# Power_Board_2.net
KiCad netlist of a schematic drawn in Altium Designer
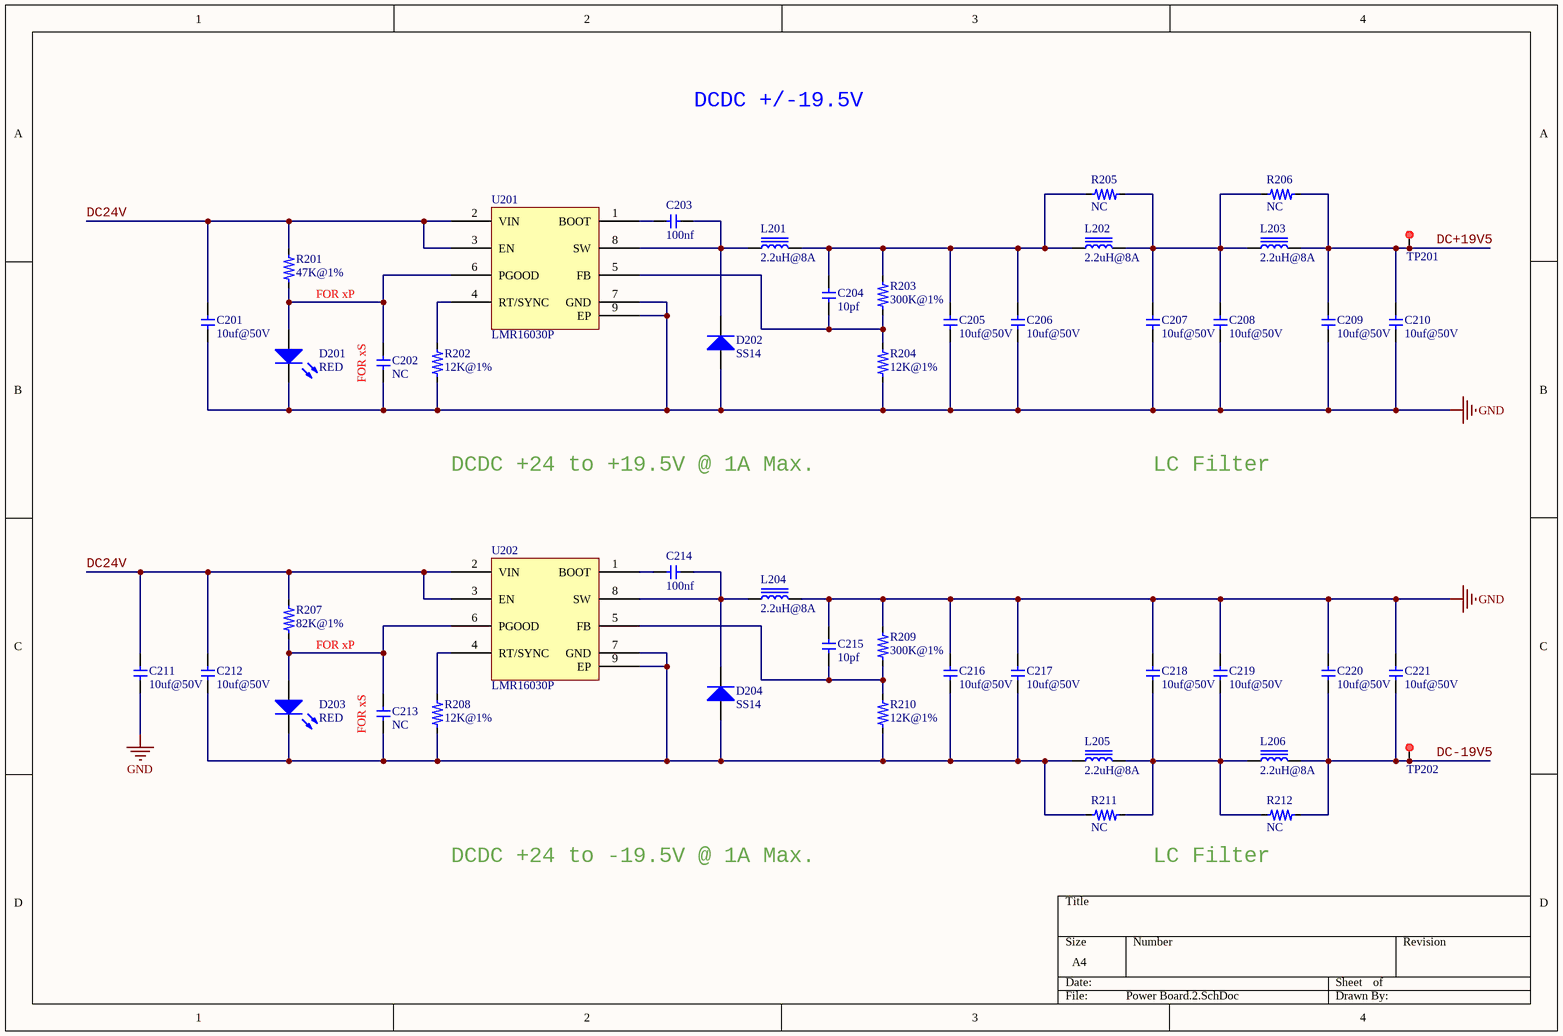
[diagram p0: Power Board.2.SchDoc]

(export (version "E")
  (design (tool "Eeschema 10.0.6"))
  (components
    (comp (ref "C201")
      (value "10uf@50V")
      (footprint "C1206")
      (fields (field (name "Comment") "Cap"))
      (libsource (lib "carrot_lib") (part "Cap"))
    )
    (comp (ref "C202")
      (value "NC")
      (footprint "C0603")
      (fields (field (name "Comment") "Cap"))
      (libsource (lib "carrot_lib") (part "Cap"))
    )
    (comp (ref "C203")
      (value "100nf")
      (footprint "C0603")
      (fields (field (name "Comment") "Cap"))
      (libsource (lib "carrot_lib") (part "Cap"))
    )
    (comp (ref "C204")
      (value "10pf")
      (footprint "C0603")
      (fields (field (name "Comment") "Cap"))
      (libsource (lib "carrot_lib") (part "Cap"))
    )
    (comp (ref "C205")
      (value "10uf@50V")
      (footprint "C1206")
      (fields (field (name "Comment") "Cap"))
      (libsource (lib "carrot_lib") (part "Cap"))
    )
    (comp (ref "C206")
      (value "10uf@50V")
      (footprint "C1206")
      (fields (field (name "Comment") "Cap"))
      (libsource (lib "carrot_lib") (part "Cap"))
    )
    (comp (ref "C207")
      (value "10uf@50V")
      (footprint "C1206")
      (fields (field (name "Comment") "Cap"))
      (libsource (lib "carrot_lib") (part "Cap"))
    )
    (comp (ref "C208")
      (value "10uf@50V")
      (footprint "C1206")
      (fields (field (name "Comment") "Cap"))
      (libsource (lib "carrot_lib") (part "Cap"))
    )
    (comp (ref "C209")
      (value "10uf@50V")
      (footprint "C1206")
      (fields (field (name "Comment") "Cap"))
      (libsource (lib "carrot_lib") (part "Cap"))
    )
    (comp (ref "C210")
      (value "10uf@50V")
      (footprint "C1206")
      (fields (field (name "Comment") "Cap"))
      (libsource (lib "carrot_lib") (part "Cap"))
    )
    (comp (ref "C211")
      (value "10uf@50V")
      (footprint "C1206")
      (fields (field (name "Comment") "Cap"))
      (libsource (lib "carrot_lib") (part "Cap"))
    )
    (comp (ref "C212")
      (value "10uf@50V")
      (footprint "C1206")
      (fields (field (name "Comment") "Cap"))
      (libsource (lib "carrot_lib") (part "Cap"))
    )
    (comp (ref "C213")
      (value "NC")
      (footprint "C0603")
      (fields (field (name "Comment") "Cap"))
      (libsource (lib "carrot_lib") (part "Cap"))
    )
    (comp (ref "C214")
      (value "100nf")
      (footprint "C0603")
      (fields (field (name "Comment") "Cap"))
      (libsource (lib "carrot_lib") (part "Cap"))
    )
    (comp (ref "C215")
      (value "10pf")
      (footprint "C0603")
      (fields (field (name "Comment") "Cap"))
      (libsource (lib "carrot_lib") (part "Cap"))
    )
    (comp (ref "C216")
      (value "10uf@50V")
      (footprint "C1206")
      (fields (field (name "Comment") "Cap"))
      (libsource (lib "carrot_lib") (part "Cap"))
    )
    (comp (ref "C217")
      (value "10uf@50V")
      (footprint "C1206")
      (fields (field (name "Comment") "Cap"))
      (libsource (lib "carrot_lib") (part "Cap"))
    )
    (comp (ref "C218")
      (value "10uf@50V")
      (footprint "C1206")
      (fields (field (name "Comment") "Cap"))
      (libsource (lib "carrot_lib") (part "Cap"))
    )
    (comp (ref "C219")
      (value "10uf@50V")
      (footprint "C1206")
      (fields (field (name "Comment") "Cap"))
      (libsource (lib "carrot_lib") (part "Cap"))
    )
    (comp (ref "C220")
      (value "10uf@50V")
      (footprint "C1206")
      (fields (field (name "Comment") "Cap"))
      (libsource (lib "carrot_lib") (part "Cap"))
    )
    (comp (ref "C221")
      (value "10uf@50V")
      (footprint "C1206")
      (fields (field (name "Comment") "Cap"))
      (libsource (lib "carrot_lib") (part "Cap"))
    )
    (comp (ref "D201")
      (value "RED")
      (footprint "LED0603")
      (fields (field (name "Comment") "LED"))
      (libsource (lib "carrot_lib") (part "LED"))
    )
    (comp (ref "D202")
      (value "SS14")
      (footprint "DIODE-SMAF")
      (description "通用二极管")
      (fields (field (name "Comment") "Diode"))
      (libsource (lib "carrot_lib") (part "Diode"))
    )
    (comp (ref "D203")
      (value "RED")
      (footprint "LED0603")
      (fields (field (name "Comment") "LED"))
      (libsource (lib "carrot_lib") (part "LED"))
    )
    (comp (ref "D204")
      (value "SS14")
      (footprint "DIODE-SMAF")
      (description "通用二极管")
      (fields (field (name "Comment") "Diode"))
      (libsource (lib "carrot_lib") (part "Diode"))
    )
    (comp (ref "L201")
      (value "2.2uH@8A")
      (footprint "L06063")
      (description "Magnetic-Core Inductor")
      (fields (field (name "Comment") "Inductor Iron"))
      (libsource (lib "carrot_lib") (part "Inductor Iron"))
    )
    (comp (ref "L202")
      (value "2.2uH@8A")
      (footprint "L06063")
      (description "Magnetic-Core Inductor")
      (fields (field (name "Comment") "Inductor Iron"))
      (libsource (lib "carrot_lib") (part "Inductor Iron"))
    )
    (comp (ref "L203")
      (value "2.2uH@8A")
      (footprint "L06063")
      (description "Magnetic-Core Inductor")
      (fields (field (name "Comment") "Inductor Iron"))
      (libsource (lib "carrot_lib") (part "Inductor Iron"))
    )
    (comp (ref "L204")
      (value "2.2uH@8A")
      (footprint "L06063")
      (description "Magnetic-Core Inductor")
      (fields (field (name "Comment") "Inductor Iron"))
      (libsource (lib "carrot_lib") (part "Inductor Iron"))
    )
    (comp (ref "L205")
      (value "2.2uH@8A")
      (footprint "L06063")
      (description "Magnetic-Core Inductor")
      (fields (field (name "Comment") "Inductor Iron"))
      (libsource (lib "carrot_lib") (part "Inductor Iron"))
    )
    (comp (ref "L206")
      (value "2.2uH@8A")
      (footprint "L06063")
      (description "Magnetic-Core Inductor")
      (fields (field (name "Comment") "Inductor Iron"))
      (libsource (lib "carrot_lib") (part "Inductor Iron"))
    )
    (comp (ref "R201")
      (value "47K@1%")
      (footprint "R0603")
      (description "电阻")
      (fields (field (name "Comment") "Res"))
      (libsource (lib "carrot_lib") (part "Res"))
    )
    (comp (ref "R202")
      (value "12K@1%")
      (footprint "R0603")
      (description "电阻")
      (fields (field (name "Comment") "Res"))
      (libsource (lib "carrot_lib") (part "Res"))
    )
    (comp (ref "R203")
      (value "300K@1%")
      (footprint "R0603")
      (description "电阻")
      (fields (field (name "Comment") "Res"))
      (libsource (lib "carrot_lib") (part "Res"))
    )
    (comp (ref "R204")
      (value "12K@1%")
      (footprint "R0603")
      (description "电阻")
      (fields (field (name "Comment") "Res"))
      (libsource (lib "carrot_lib") (part "Res"))
    )
    (comp (ref "R205")
      (value "NC")
      (footprint "R0603")
      (description "电阻")
      (fields (field (name "Comment") "Res"))
      (libsource (lib "carrot_lib") (part "Res"))
    )
    (comp (ref "R206")
      (value "NC")
      (footprint "R0603")
      (description "电阻")
      (fields (field (name "Comment") "Res"))
      (libsource (lib "carrot_lib") (part "Res"))
    )
    (comp (ref "R207")
      (value "82K@1%")
      (footprint "R0603")
      (description "电阻")
      (fields (field (name "Comment") "Res"))
      (libsource (lib "carrot_lib") (part "Res"))
    )
    (comp (ref "R208")
      (value "12K@1%")
      (footprint "R0603")
      (description "电阻")
      (fields (field (name "Comment") "Res"))
      (libsource (lib "carrot_lib") (part "Res"))
    )
    (comp (ref "R209")
      (value "300K@1%")
      (footprint "R0603")
      (description "电阻")
      (fields (field (name "Comment") "Res"))
      (libsource (lib "carrot_lib") (part "Res"))
    )
    (comp (ref "R210")
      (value "12K@1%")
      (footprint "R0603")
      (description "电阻")
      (fields (field (name "Comment") "Res"))
      (libsource (lib "carrot_lib") (part "Res"))
    )
    (comp (ref "R211")
      (value "NC")
      (footprint "R0603")
      (description "电阻")
      (fields (field (name "Comment") "Res"))
      (libsource (lib "carrot_lib") (part "Res"))
    )
    (comp (ref "R212")
      (value "NC")
      (footprint "R0603")
      (description "电阻")
      (fields (field (name "Comment") "Res"))
      (libsource (lib "carrot_lib") (part "Res"))
    )
    (comp (ref "TP201")
      (value "TestPoint")
      (footprint "TestPoint-SMD100")
      (description "测试点")
      (libsource (lib "carrot_lib") (part "TestPoint"))
    )
    (comp (ref "TP202")
      (value "TestPoint")
      (footprint "TestPoint-SMD100")
      (description "测试点")
      (libsource (lib "carrot_lib") (part "TestPoint"))
    )
    (comp (ref "U201")
      (value "LMR16030P")
      (footprint "LMR16030-SOIC8")
      (description "LMR16030 SIMPLE SWITCHER® 60-V, 3-A Step-Down Converter With 40-µA IQ")
      (libsource (lib "carrot_lib") (part "LMR16030P"))
    )
    (comp (ref "U202")
      (value "LMR16030P")
      (footprint "LMR16030-SOIC8")
      (description "LMR16030 SIMPLE SWITCHER® 60-V, 3-A Step-Down Converter With 40-µA IQ")
      (libsource (lib "carrot_lib") (part "LMR16030P"))
    )
  )
  (nets
    (net (code "1") (name "/DC+19V5") (class "Default")
      (node (ref "C209") (pin "2") (pinfunction "2_2") (pintype "passive"))
      (node (ref "C210") (pin "2") (pinfunction "2_2") (pintype "passive"))
      (node (ref "L203") (pin "2") (pinfunction "2_2") (pintype "passive"))
      (node (ref "R206") (pin "1") (pinfunction "1_1") (pintype "passive"))
      (node (ref "TP201") (pin "1") (pinfunction "1_1") (pintype "passive"))
    )
    (net (code "2") (name "/DC-19V5") (class "Default")
      (node (ref "C220") (pin "1") (pinfunction "1_1") (pintype "passive"))
      (node (ref "C221") (pin "1") (pinfunction "1_1") (pintype "passive"))
      (node (ref "L206") (pin "2") (pinfunction "2_2") (pintype "passive"))
      (node (ref "R212") (pin "1") (pinfunction "1_1") (pintype "passive"))
      (node (ref "TP202") (pin "1") (pinfunction "1_1") (pintype "passive"))
    )
    (net (code "3") (name "/DC24V") (class "Default")
      (node (ref "C201") (pin "2") (pinfunction "2_2") (pintype "passive"))
      (node (ref "C211") (pin "2") (pinfunction "2_2") (pintype "passive"))
      (node (ref "C212") (pin "2") (pinfunction "2_2") (pintype "passive"))
      (node (ref "R201") (pin "2") (pinfunction "2_2") (pintype "passive"))
      (node (ref "R207") (pin "2") (pinfunction "2_2") (pintype "passive"))
      (node (ref "U201") (pin "2") (pinfunction "VIN_2") (pintype "passive"))
      (node (ref "U201") (pin "3") (pinfunction "EN_3") (pintype "passive"))
      (node (ref "U202") (pin "2") (pinfunction "VIN_2") (pintype "passive"))
      (node (ref "U202") (pin "3") (pinfunction "EN_3") (pintype "passive"))
    )
    (net (code "4") (name "GND") (class "Default")
      (node (ref "C201") (pin "1") (pinfunction "1_1") (pintype "passive"))
      (node (ref "C202") (pin "1") (pinfunction "1_1") (pintype "passive"))
      (node (ref "C205") (pin "1") (pinfunction "1_1") (pintype "passive"))
      (node (ref "C206") (pin "1") (pinfunction "1_1") (pintype "passive"))
      (node (ref "C207") (pin "1") (pinfunction "1_1") (pintype "passive"))
      (node (ref "C208") (pin "1") (pinfunction "1_1") (pintype "passive"))
      (node (ref "C209") (pin "1") (pinfunction "1_1") (pintype "passive"))
      (node (ref "C210") (pin "1") (pinfunction "1_1") (pintype "passive"))
      (node (ref "C211") (pin "1") (pinfunction "1_1") (pintype "passive"))
      (node (ref "C215") (pin "1") (pinfunction "1_1") (pintype "passive"))
      (node (ref "C216") (pin "2") (pinfunction "2_2") (pintype "passive"))
      (node (ref "C217") (pin "2") (pinfunction "2_2") (pintype "passive"))
      (node (ref "C218") (pin "2") (pinfunction "2_2") (pintype "passive"))
      (node (ref "C219") (pin "2") (pinfunction "2_2") (pintype "passive"))
      (node (ref "C220") (pin "2") (pinfunction "2_2") (pintype "passive"))
      (node (ref "C221") (pin "2") (pinfunction "2_2") (pintype "passive"))
      (node (ref "D201") (pin "2") (pinfunction "K_2") (pintype "passive"))
      (node (ref "D202") (pin "1") (pinfunction "A_1") (pintype "passive"))
      (node (ref "L204") (pin "2") (pinfunction "2_2") (pintype "passive"))
      (node (ref "R202") (pin "1") (pinfunction "1_1") (pintype "passive"))
      (node (ref "R204") (pin "1") (pinfunction "1_1") (pintype "passive"))
      (node (ref "R209") (pin "2") (pinfunction "2_2") (pintype "passive"))
      (node (ref "U201") (pin "7") (pinfunction "GND_7") (pintype "passive"))
      (node (ref "U201") (pin "9") (pinfunction "EP_9") (pintype "passive"))
    )
    (net (code "5") (name "Net-(C204-Pad1)") (class "Default")
      (node (ref "C204") (pin "1") (pinfunction "1_1") (pintype "passive"))
      (node (ref "C205") (pin "2") (pinfunction "2_2") (pintype "passive"))
      (node (ref "C206") (pin "2") (pinfunction "2_2") (pintype "passive"))
      (node (ref "L201") (pin "2") (pinfunction "2_2") (pintype "passive"))
      (node (ref "L202") (pin "1") (pinfunction "1_1") (pintype "passive"))
      (node (ref "R203") (pin "2") (pinfunction "2_2") (pintype "passive"))
      (node (ref "R205") (pin "2") (pinfunction "2_2") (pintype "passive"))
    )
    (net (code "6") (name "Net-(C207-Pad2)") (class "Default")
      (node (ref "C207") (pin "2") (pinfunction "2_2") (pintype "passive"))
      (node (ref "C208") (pin "2") (pinfunction "2_2") (pintype "passive"))
      (node (ref "L202") (pin "2") (pinfunction "2_2") (pintype "passive"))
      (node (ref "L203") (pin "1") (pinfunction "1_1") (pintype "passive"))
      (node (ref "R205") (pin "1") (pinfunction "1_1") (pintype "passive"))
      (node (ref "R206") (pin "2") (pinfunction "2_2") (pintype "passive"))
    )
    (net (code "7") (name "Net-(C218-Pad1)") (class "Default")
      (node (ref "C218") (pin "1") (pinfunction "1_1") (pintype "passive"))
      (node (ref "C219") (pin "1") (pinfunction "1_1") (pintype "passive"))
      (node (ref "L205") (pin "2") (pinfunction "2_2") (pintype "passive"))
      (node (ref "L206") (pin "1") (pinfunction "1_1") (pintype "passive"))
      (node (ref "R211") (pin "1") (pinfunction "1_1") (pintype "passive"))
      (node (ref "R212") (pin "2") (pinfunction "2_2") (pintype "passive"))
    )
    (net (code "8") (name "Net-(D201-A)") (class "Default")
      (node (ref "C202") (pin "2") (pinfunction "2_2") (pintype "passive"))
      (node (ref "D201") (pin "1") (pinfunction "A_1") (pintype "passive"))
      (node (ref "R201") (pin "1") (pinfunction "1_1") (pintype "passive"))
      (node (ref "U201") (pin "6") (pinfunction "PGOOD_6") (pintype "passive"))
    )
    (net (code "9") (name "Net-(D202-K)") (class "Default")
      (node (ref "C203") (pin "1") (pinfunction "1_1") (pintype "passive"))
      (node (ref "D202") (pin "2") (pinfunction "K_2") (pintype "passive"))
      (node (ref "L201") (pin "1") (pinfunction "1_1") (pintype "passive"))
      (node (ref "U201") (pin "8") (pinfunction "SW_8") (pintype "passive"))
    )
    (net (code "10") (name "Net-(D203-A)") (class "Default")
      (node (ref "C213") (pin "2") (pinfunction "2_2") (pintype "passive"))
      (node (ref "D203") (pin "1") (pinfunction "A_1") (pintype "passive"))
      (node (ref "R207") (pin "1") (pinfunction "1_1") (pintype "passive"))
      (node (ref "U202") (pin "6") (pinfunction "PGOOD_6") (pintype "passive"))
    )
    (net (code "11") (name "Net-(D203-K)") (class "Default")
      (node (ref "C212") (pin "1") (pinfunction "1_1") (pintype "passive"))
      (node (ref "C213") (pin "1") (pinfunction "1_1") (pintype "passive"))
      (node (ref "C216") (pin "1") (pinfunction "1_1") (pintype "passive"))
      (node (ref "C217") (pin "1") (pinfunction "1_1") (pintype "passive"))
      (node (ref "D203") (pin "2") (pinfunction "K_2") (pintype "passive"))
      (node (ref "D204") (pin "1") (pinfunction "A_1") (pintype "passive"))
      (node (ref "L205") (pin "1") (pinfunction "1_1") (pintype "passive"))
      (node (ref "R208") (pin "1") (pinfunction "1_1") (pintype "passive"))
      (node (ref "R210") (pin "1") (pinfunction "1_1") (pintype "passive"))
      (node (ref "R211") (pin "2") (pinfunction "2_2") (pintype "passive"))
      (node (ref "U202") (pin "7") (pinfunction "GND_7") (pintype "passive"))
      (node (ref "U202") (pin "9") (pinfunction "EP_9") (pintype "passive"))
    )
    (net (code "12") (name "Net-(D204-K)") (class "Default")
      (node (ref "C214") (pin "1") (pinfunction "1_1") (pintype "passive"))
      (node (ref "D204") (pin "2") (pinfunction "K_2") (pintype "passive"))
      (node (ref "L204") (pin "1") (pinfunction "1_1") (pintype "passive"))
      (node (ref "U202") (pin "8") (pinfunction "SW_8") (pintype "passive"))
    )
    (net (code "13") (name "Net-(U201-BOOT)") (class "Default")
      (node (ref "C203") (pin "2") (pinfunction "2_2") (pintype "passive"))
      (node (ref "U201") (pin "1") (pinfunction "BOOT_1") (pintype "passive"))
    )
    (net (code "14") (name "Net-(U201-FB)") (class "Default")
      (node (ref "C204") (pin "2") (pinfunction "2_2") (pintype "passive"))
      (node (ref "R203") (pin "1") (pinfunction "1_1") (pintype "passive"))
      (node (ref "R204") (pin "2") (pinfunction "2_2") (pintype "passive"))
      (node (ref "U201") (pin "5") (pinfunction "FB_5") (pintype "passive"))
    )
    (net (code "15") (name "Net-(U201-RT{slash}SYNC)") (class "Default")
      (node (ref "R202") (pin "2") (pinfunction "2_2") (pintype "passive"))
      (node (ref "U201") (pin "4") (pinfunction "RT/SYNC_4") (pintype "passive"))
    )
    (net (code "16") (name "Net-(U202-BOOT)") (class "Default")
      (node (ref "C214") (pin "2") (pinfunction "2_2") (pintype "passive"))
      (node (ref "U202") (pin "1") (pinfunction "BOOT_1") (pintype "passive"))
    )
    (net (code "17") (name "Net-(U202-FB)") (class "Default")
      (node (ref "C215") (pin "2") (pinfunction "2_2") (pintype "passive"))
      (node (ref "R209") (pin "1") (pinfunction "1_1") (pintype "passive"))
      (node (ref "R210") (pin "2") (pinfunction "2_2") (pintype "passive"))
      (node (ref "U202") (pin "5") (pinfunction "FB_5") (pintype "passive"))
    )
    (net (code "18") (name "Net-(U202-RT{slash}SYNC)") (class "Default")
      (node (ref "R208") (pin "2") (pinfunction "2_2") (pintype "passive"))
      (node (ref "U202") (pin "4") (pinfunction "RT/SYNC_4") (pintype "passive"))
    )
  )
)
